# Radio.net
KiCad netlist of a schematic drawn in Altium Designer
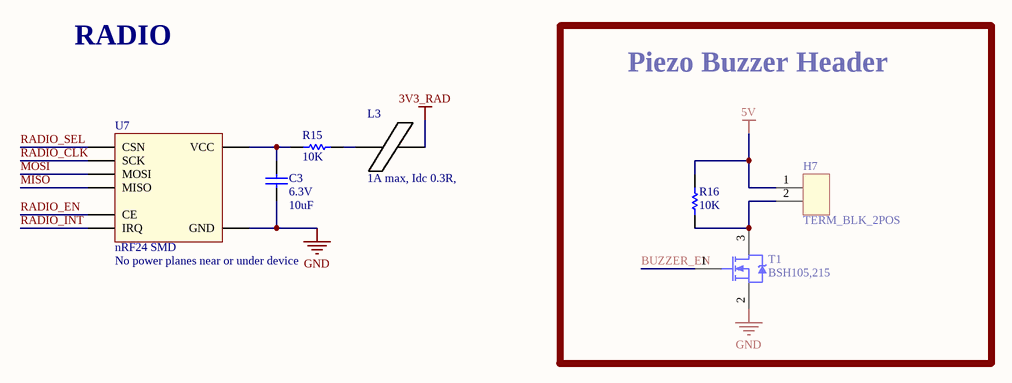
[diagram p0: Radio.SchDoc]

(export (version "E")
  (design (tool "Eeschema 10.0.6"))
  (components
    (comp (ref "C3")
      (value "10uF")
      (footprint "CAPC1608L")
      (description "CAP CER 10UF X5R +-20% 6V3 0603")
      (fields (field (name "VOLTAGE - RATED") "6.3V"))
      (libsource (lib "ECE AD19Components_19V1") (part "CC_10uF_0603"))
    )
    (comp (ref "H7")
      (value "TERM_BLK_2POS")
      (footprint "TERM_BLK_2POS")
      (description "2 Position Terminal Block 7.62mm spacing")
      (libsource (lib "ENCE461AD19_19V2") (part "TERM_BLK_2POS"))
    )
    (comp (ref "L3")
      (value "1A max, Idc 0.3R,")
      (footprint "INDC3216L")
      (description "Ferrite Bead, Rdc 0.3R, Z100MHZ 600R, Imax 1A, SMD 1206")
      (fields
        (field (name "MANUFACTURER") "FAIR-RITE")
        (field (name "MANUFACTURER PART NUMBER") "2512066017Y1")
      )
      (libsource (lib "ECE AD19Components_19V1") (part "IN_Ferrite-Bead"))
    )
    (comp (ref "R15")
      (value "10K")
      (footprint "RESC1608L")
      (description "RES 10.0K OHM 1/10W 5% 0603 SMD")
      (libsource (lib "ECE AD19Components_19V1") (part "RS_10K"))
    )
    (comp (ref "R16")
      (value "10K")
      (footprint "RESC1608L")
      (description "RES 10.0K OHM 1/10W 5% 0603 SMD")
      (libsource (lib "ECE AD19Components_19V1") (part "RS_10K"))
    )
    (comp (ref "T1")
      (value "BSH105,215")
      (footprint "SOT23_L")
      (description "MOSFET N-CH 20V 1.05A SOT-23")
      (fields
        (field (name "MANUFACTURER") "NXP Semiconductors")
        (field (name "MANUFACTURER PART NUMBER") "BSH105,215")
      )
      (libsource (lib "ECE AD19Components_19V1") (part "TM_BSH105"))
    )
    (comp (ref "U7")
      (value "nRF24 SMD")
      (footprint "NRF24")
      (description "nRF24 SMD Module")
      (fields (field (name "WARNING") "No power planes near or under device"))
      (libsource (lib "ENCE461AD19_19V2") (part "NRF24"))
    )
  )
  (nets
    (net (code "1") (name "/BUZZER_EN") (class "Default")
      (node (ref "T1") (pin "1") (pinfunction "1_1") (pintype "passive"))
    )
    (net (code "2") (name "/MISO") (class "Default")
      (node (ref "U7") (pin "7") (pinfunction "MISO_7") (pintype "passive"))
    )
    (net (code "3") (name "/MOSI") (class "Default")
      (node (ref "U7") (pin "6") (pinfunction "MOSI_6") (pintype "passive"))
    )
    (net (code "4") (name "/RADIO_CLK") (class "Default")
      (node (ref "U7") (pin "5") (pinfunction "SCK_5") (pintype "passive"))
    )
    (net (code "5") (name "/RADIO_EN") (class "Default")
      (node (ref "U7") (pin "3") (pinfunction "CE_3") (pintype "passive"))
    )
    (net (code "6") (name "/RADIO_INT") (class "Default")
      (node (ref "U7") (pin "8") (pinfunction "IRQ_8") (pintype "passive"))
    )
    (net (code "7") (name "/RADIO_SEL") (class "Default")
      (node (ref "U7") (pin "4") (pinfunction "CSN_4") (pintype "passive"))
    )
    (net (code "8") (name "3V3_RAD") (class "Default")
      (node (ref "L3") (pin "2") (pinfunction "2_2") (pintype "passive"))
    )
    (net (code "9") (name "5V") (class "Default")
      (node (ref "H7") (pin "1") (pintype "passive"))
      (node (ref "R16") (pin "2") (pinfunction "2_2") (pintype "passive"))
    )
    (net (code "10") (name "GND") (class "Default")
      (node (ref "C3") (pin "1") (pinfunction "1_1") (pintype "passive"))
      (node (ref "T1") (pin "2") (pinfunction "2_2") (pintype "passive"))
      (node (ref "U7") (pin "2") (pinfunction "GND_2") (pintype "passive"))
    )
    (net (code "11") (name "Net-(H7-Pad2)") (class "Default")
      (node (ref "H7") (pin "2") (pintype "passive"))
      (node (ref "R16") (pin "1") (pinfunction "1_1") (pintype "passive"))
      (node (ref "T1") (pin "3") (pinfunction "3_3") (pintype "passive"))
    )
    (net (code "12") (name "Net-(L3-Pad1)") (class "Default")
      (node (ref "L3") (pin "1") (pinfunction "1_1") (pintype "passive"))
      (node (ref "R15") (pin "2") (pinfunction "2_2") (pintype "passive"))
    )
    (net (code "13") (name "Net-(U7-VCC)") (class "Default")
      (node (ref "C3") (pin "2") (pinfunction "2_2") (pintype "passive"))
      (node (ref "R15") (pin "1") (pinfunction "1_1") (pintype "passive"))
      (node (ref "U7") (pin "1") (pinfunction "VCC_1") (pintype "passive"))
    )
  )
)
